# can-bb.net
KiCad netlist of a schematic drawn in EAGLE
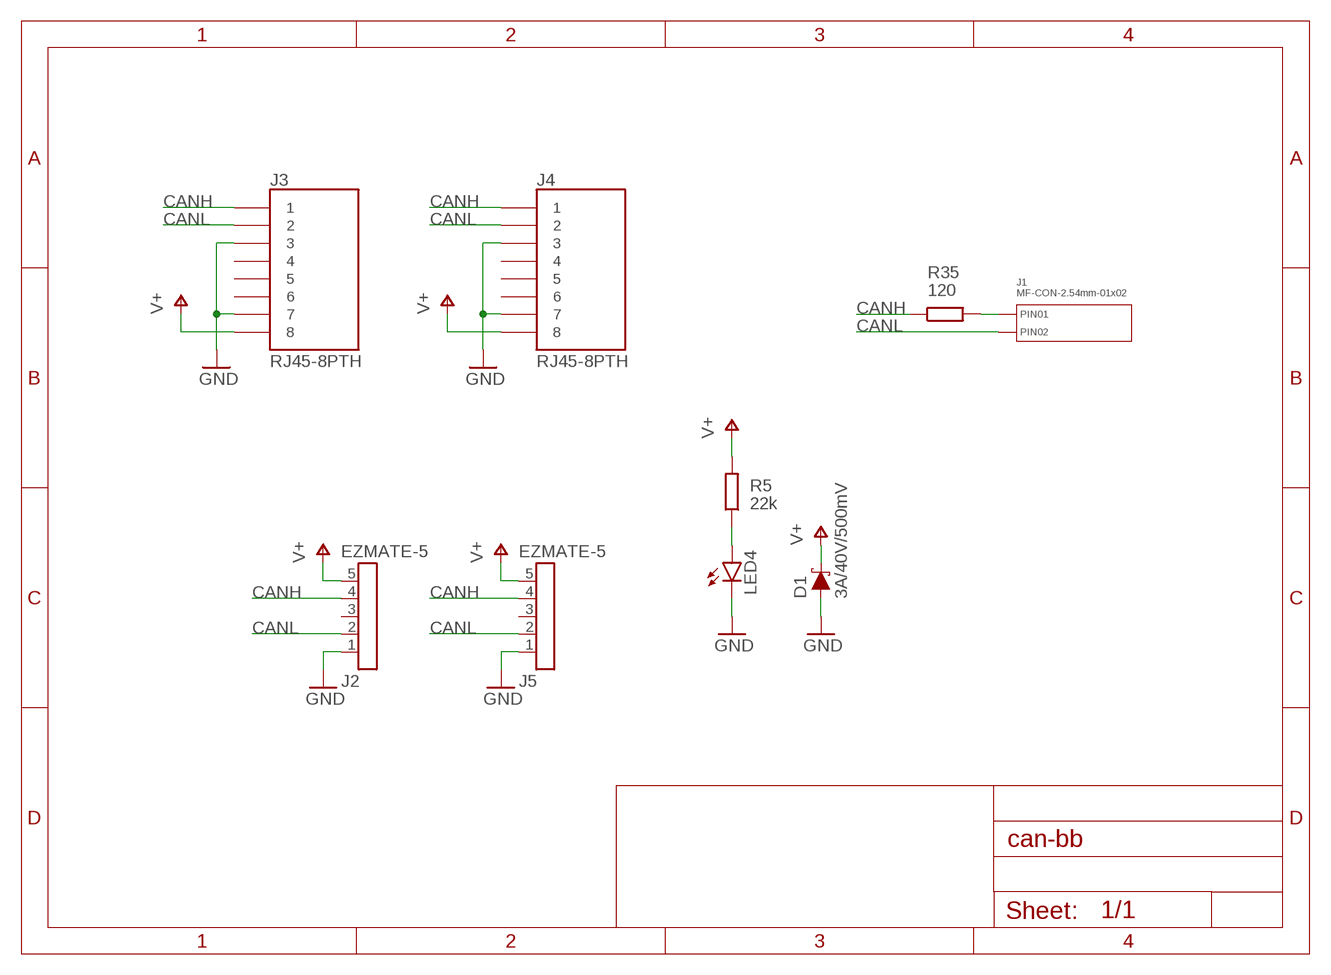
[diagram p0: schematic, sheet 1]

(export (version "E")
  (design (tool "Eeschema 10.0.6"))
  (components
    (comp (ref "D1")
      (value "3A/40V/500mV")
      (footprint "eagle-import:SMA-DIODE")
      (libsource (lib "eagle-import") (part "DIODE-SCHOTTKY-B340A"))
    )
    (comp (ref "J1")
      (value "MF-CON-2.54mm-01x02")
      (footprint "eagle-import:PTH_2.54MM_01X02")
      (fields (field (name "HOUSEPART") "YES"))
      (libsource (lib "eagle-import") (part "CON_01X02_PTH_2.54MM"))
    )
    (comp (ref "J2")
      (value "EZMATE-5")
      (footprint "eagle-import:EZMATE-5")
      (libsource (lib "eagle-import") (part "EZMATE-5"))
    )
    (comp (ref "J3")
      (value "RJ45-8PTH")
      (footprint "eagle-import:RJ45-8")
      (libsource (lib "eagle-import") (part "RJ45-8PTH"))
    )
    (comp (ref "J4")
      (value "RJ45-8PTH")
      (footprint "eagle-import:RJ45-8")
      (libsource (lib "eagle-import") (part "RJ45-8PTH"))
    )
    (comp (ref "J5")
      (value "EZMATE-5")
      (footprint "eagle-import:EZMATE-5")
      (libsource (lib "eagle-import") (part "EZMATE-5"))
    )
    (comp (ref "LED4")
      (value "LEDCHIPLED_0603")
      (footprint "eagle-import:CHIPLED_0603")
      (libsource (lib "eagle-import") (part "LEDCHIPLED_0603"))
    )
    (comp (ref "R5")
      (value "22k")
      (footprint "eagle-import:0603")
      (libsource (lib "eagle-import") (part "R0603"))
    )
    (comp (ref "R35")
      (value "120")
      (footprint "eagle-import:R0805")
      (libsource (lib "eagle-import") (part "R-EU_R0805"))
    )
  )
  (nets
    (net (code "1") (name "/CANH") (class "Default")
      (node (ref "J2") (pin "4") (pinfunction "P$4_4") (pintype "bidirectional"))
      (node (ref "J3") (pin "1") (pinfunction "1_1") (pintype "bidirectional"))
      (node (ref "J4") (pin "1") (pinfunction "1_1") (pintype "bidirectional"))
      (node (ref "J5") (pin "4") (pinfunction "P$4_4") (pintype "bidirectional"))
      (node (ref "R35") (pin "1") (pinfunction "1_1") (pintype "passive"))
    )
    (net (code "2") (name "/CANL") (class "Default")
      (node (ref "J1") (pin "P$2") (pinfunction "PIN2_P$2") (pintype "bidirectional"))
      (node (ref "J2") (pin "2") (pinfunction "P$2_2") (pintype "bidirectional"))
      (node (ref "J3") (pin "2") (pinfunction "2_2") (pintype "bidirectional"))
      (node (ref "J4") (pin "2") (pinfunction "2_2") (pintype "bidirectional"))
      (node (ref "J5") (pin "2") (pinfunction "P$2_2") (pintype "bidirectional"))
    )
    (net (code "3") (name "GND") (class "Default")
      (node (ref "D1") (pin "A") (pinfunction "A_A") (pintype "passive"))
      (node (ref "J2") (pin "1") (pinfunction "P$1_1") (pintype "bidirectional"))
      (node (ref "J3") (pin "3") (pinfunction "3_3") (pintype "bidirectional"))
      (node (ref "J3") (pin "7") (pinfunction "7_7") (pintype "bidirectional"))
      (node (ref "J4") (pin "3") (pinfunction "3_3") (pintype "bidirectional"))
      (node (ref "J4") (pin "7") (pinfunction "7_7") (pintype "bidirectional"))
      (node (ref "J5") (pin "1") (pinfunction "P$1_1") (pintype "bidirectional"))
      (node (ref "LED4") (pin "C") (pinfunction "C_C") (pintype "passive"))
    )
    (net (code "4") (name "Net-(J1-PIN1)") (class "Default")
      (node (ref "J1") (pin "P$1") (pinfunction "PIN1_P$1") (pintype "bidirectional"))
      (node (ref "R35") (pin "2") (pinfunction "2_2") (pintype "passive"))
    )
    (net (code "5") (name "Net-(LED4-PadA)") (class "Default")
      (node (ref "LED4") (pin "A") (pinfunction "A_A") (pintype "passive"))
      (node (ref "R5") (pin "1") (pinfunction "1_1") (pintype "passive"))
    )
    (net (code "6") (name "V+") (class "Default")
      (node (ref "D1") (pin "C") (pinfunction "C_C") (pintype "passive"))
      (node (ref "J2") (pin "5") (pinfunction "P$5_5") (pintype "bidirectional"))
      (node (ref "J3") (pin "8") (pinfunction "8_8") (pintype "bidirectional"))
      (node (ref "J4") (pin "8") (pinfunction "8_8") (pintype "bidirectional"))
      (node (ref "J5") (pin "5") (pinfunction "P$5_5") (pintype "bidirectional"))
      (node (ref "R5") (pin "2") (pinfunction "2_2") (pintype "passive"))
    )
    (net (code "7") (name "unconnected-(J2-P$3-Pad3)") (class "Default")
      (node (ref "J2") (pin "3") (pinfunction "P$3_3") (pintype "bidirectional"))
    )
    (net (code "8") (name "unconnected-(J3-Pad4)") (class "Default")
      (node (ref "J3") (pin "4") (pinfunction "4_4") (pintype "bidirectional"))
    )
    (net (code "9") (name "unconnected-(J3-Pad5)") (class "Default")
      (node (ref "J3") (pin "5") (pinfunction "5_5") (pintype "bidirectional"))
    )
    (net (code "10") (name "unconnected-(J3-Pad6)") (class "Default")
      (node (ref "J3") (pin "6") (pinfunction "6_6") (pintype "bidirectional"))
    )
    (net (code "11") (name "unconnected-(J4-Pad4)") (class "Default")
      (node (ref "J4") (pin "4") (pinfunction "4_4") (pintype "bidirectional"))
    )
    (net (code "12") (name "unconnected-(J4-Pad5)") (class "Default")
      (node (ref "J4") (pin "5") (pinfunction "5_5") (pintype "bidirectional"))
    )
    (net (code "13") (name "unconnected-(J4-Pad6)") (class "Default")
      (node (ref "J4") (pin "6") (pinfunction "6_6") (pintype "bidirectional"))
    )
    (net (code "14") (name "unconnected-(J5-P$3-Pad3)") (class "Default")
      (node (ref "J5") (pin "3") (pinfunction "P$3_3") (pintype "bidirectional"))
    )
  )
)
